# DMX.net
KiCad netlist of a schematic drawn in Altium Designer
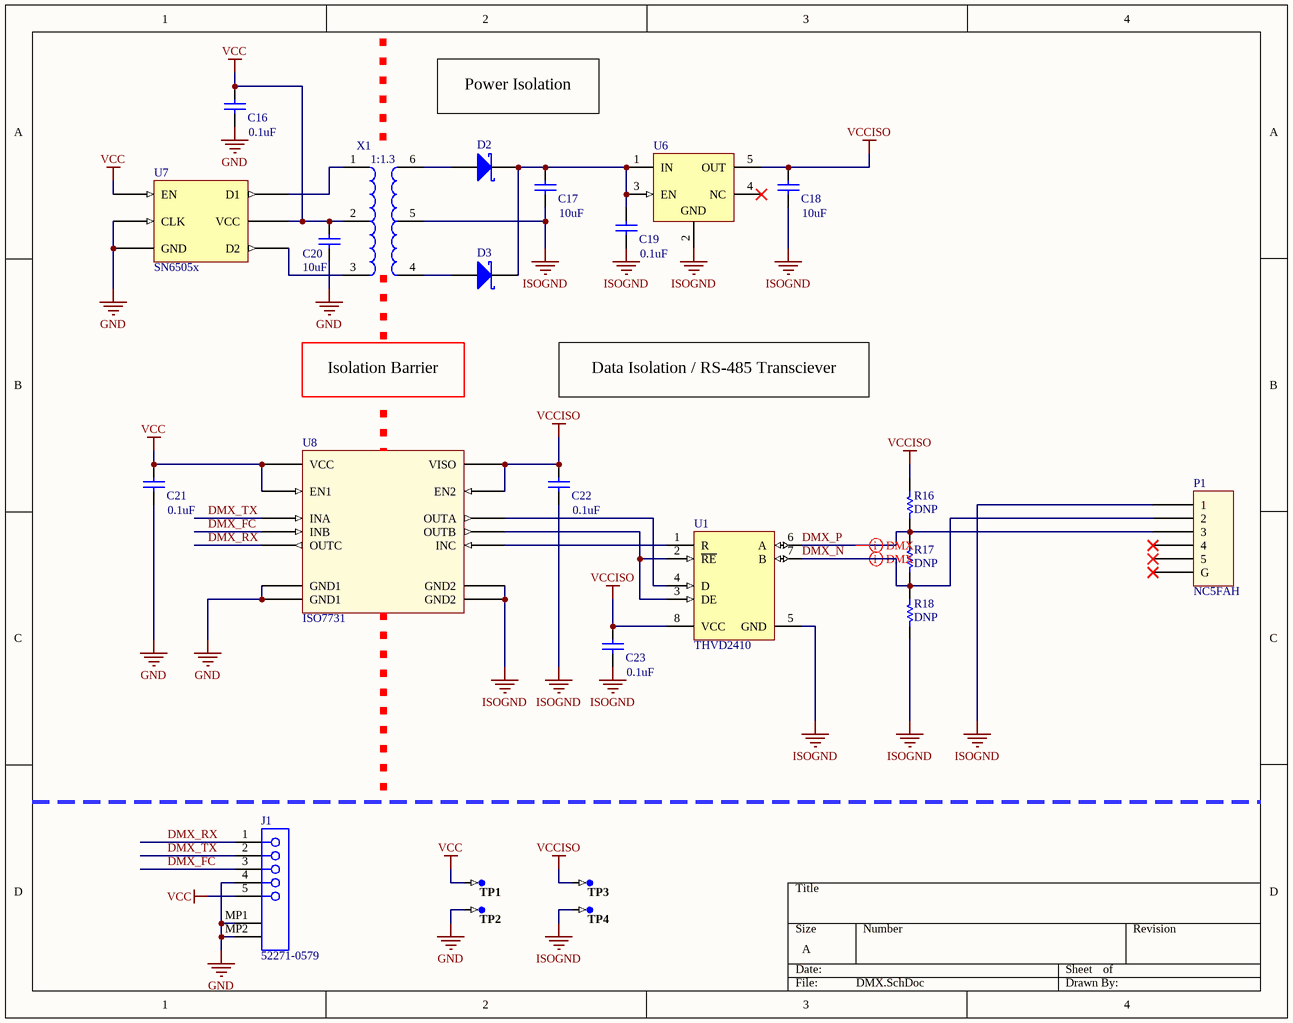
[diagram p0: DMX.SchDoc]

(export (version "E")
  (design (tool "Eeschema 10.0.6"))
  (components
    (comp (ref "C16")
      (value "0.1uF")
      (footprint "CAPC0603(1608)100_L")
      (description "CAP 27pF 16V ±0.5pF 0603 (1608 Metric) Thickness 1mm SMD")
      (fields (field (name "TOLERANCE") "Â±0.5pF"))
      (libsource (lib "Altium Content Vault") (part "CMP-1035-00873-1"))
    )
    (comp (ref "C17")
      (value "10uF")
      (footprint "CAPC0603(1608)100_L")
      (description "CAP 27pF 16V ±0.5pF 0603 (1608 Metric) Thickness 1mm SMD")
      (fields (field (name "TOLERANCE") "Â±0.5pF"))
      (libsource (lib "Altium Content Vault") (part "CMP-1035-00873-1"))
    )
    (comp (ref "C18")
      (value "10uF")
      (footprint "CAPC0603(1608)100_L")
      (description "CAP 27pF 16V ±0.5pF 0603 (1608 Metric) Thickness 1mm SMD")
      (fields (field (name "TOLERANCE") "Â±0.5pF"))
      (libsource (lib "Altium Content Vault") (part "CMP-1035-00873-1"))
    )
    (comp (ref "C19")
      (value "0.1uF")
      (footprint "CAPC0603(1608)100_L")
      (description "CAP 27pF 16V ±0.5pF 0603 (1608 Metric) Thickness 1mm SMD")
      (fields (field (name "TOLERANCE") "Â±0.5pF"))
      (libsource (lib "Altium Content Vault") (part "CMP-1035-00873-1"))
    )
    (comp (ref "C20")
      (value "10uF")
      (footprint "CAPC0603(1608)100_L")
      (description "CAP 27pF 16V ±0.5pF 0603 (1608 Metric) Thickness 1mm SMD")
      (fields (field (name "TOLERANCE") "Â±0.5pF"))
      (libsource (lib "Altium Content Vault") (part "CMP-1035-00873-1"))
    )
    (comp (ref "C21")
      (value "0.1uF")
      (footprint "CAPC0603(1608)100_L")
      (description "CAP 27pF 16V ±0.5pF 0603 (1608 Metric) Thickness 1mm SMD")
      (fields (field (name "TOLERANCE") "Â±0.5pF"))
      (libsource (lib "Altium Content Vault") (part "CMP-1035-00873-1"))
    )
    (comp (ref "C22")
      (value "0.1uF")
      (footprint "CAPC0603(1608)100_L")
      (description "CAP 27pF 16V ±0.5pF 0603 (1608 Metric) Thickness 1mm SMD")
      (fields (field (name "TOLERANCE") "Â±0.5pF"))
      (libsource (lib "Altium Content Vault") (part "CMP-1035-00873-1"))
    )
    (comp (ref "C23")
      (value "0.1uF")
      (footprint "CAPC0603(1608)100_L")
      (description "CAP 27pF 16V ±0.5pF 0603 (1608 Metric) Thickness 1mm SMD")
      (fields (field (name "TOLERANCE") "Â±0.5pF"))
      (libsource (lib "Altium Content Vault") (part "CMP-1035-00873-1"))
    )
    (comp (ref "D2")
      (value "MBR0520L")
      (footprint "ONSC-SOD-123-2-425-04_V")
      (description "Schottky Diode, 20V, 0.2A, 2-pin SOD-123, RoHS, Tape and Reel")
      (fields (field (name "MANUFACTURER") "FairchildSemiconductor"))
      (libsource (lib "Altium Content Vault") (part "CMP-2000-04926-1"))
    )
    (comp (ref "D3")
      (value "MBR0520L")
      (footprint "ONSC-SOD-123-2-425-04_V")
      (description "Schottky Diode, 20V, 0.2A, 2-pin SOD-123, RoHS, Tape and Reel")
      (fields (field (name "MANUFACTURER") "FairchildSemiconductor"))
      (libsource (lib "Altium Content Vault") (part "CMP-2000-04926-1"))
    )
    (comp (ref "J1")
      (value "52271-0579")
      (footprint "MOLX-52271-0579")
      (fields (field (name "MANUFACTURER") "Molex"))
      (libsource (lib "Molex FFC - FPC Connectors (SMT)") (part "52271-0579"))
    )
    (comp (ref "P1") (value "NC5FAH") (footprint "NC5FAH") (libsource (lib "Neutrik") (part "NC5FAH")))
    (comp (ref "R16")
      (value "DNP")
      (footprint "RESC0603(1608)_N")
      (description "300K 0.1W 5% 0603 (1608 Metric)  SMD")
      (fields (field (name "POWER") "0.1 W") (field (name "TOLERANCE") "5 %"))
      (libsource (lib "Altium Content Vault") (part "CMP-1012-00133-1"))
    )
    (comp (ref "R17")
      (value "DNP")
      (footprint "RESC0603(1608)_N")
      (description "300K 0.1W 5% 0603 (1608 Metric)  SMD")
      (fields (field (name "POWER") "0.1 W") (field (name "TOLERANCE") "5 %"))
      (libsource (lib "Altium Content Vault") (part "CMP-1012-00133-1"))
    )
    (comp (ref "R18")
      (value "DNP")
      (footprint "RESC0603(1608)_N")
      (description "300K 0.1W 5% 0603 (1608 Metric)  SMD")
      (fields (field (name "POWER") "0.1 W") (field (name "TOLERANCE") "5 %"))
      (libsource (lib "Altium Content Vault") (part "CMP-1012-00133-1"))
    )
    (comp (ref "TP1")
      (value "TP-SM-C-100")
      (footprint "TP-SM-C-100")
      (description "Test Point, Surface Mount, Circular, Pad Diameter 1 mm")
      (fields (field (name "MANUFACTURER") "No Vendor"))
      (libsource (lib "Altium Content Vault") (part "CMP-0484-00002-2"))
    )
    (comp (ref "TP2")
      (value "TP-SM-C-100")
      (footprint "TP-SM-C-100")
      (description "Test Point, Surface Mount, Circular, Pad Diameter 1 mm")
      (fields (field (name "MANUFACTURER") "No Vendor"))
      (libsource (lib "Altium Content Vault") (part "CMP-0484-00002-2"))
    )
    (comp (ref "TP3")
      (value "TP-SM-C-100")
      (footprint "TP-SM-C-100")
      (description "Test Point, Surface Mount, Circular, Pad Diameter 1 mm")
      (fields (field (name "MANUFACTURER") "No Vendor"))
      (libsource (lib "Altium Content Vault") (part "CMP-0484-00002-2"))
    )
    (comp (ref "TP4")
      (value "TP-SM-C-100")
      (footprint "TP-SM-C-100")
      (description "Test Point, Surface Mount, Circular, Pad Diameter 1 mm")
      (fields (field (name "MANUFACTURER") "No Vendor"))
      (libsource (lib "Altium Content Vault") (part "CMP-0484-00002-2"))
    )
    (comp (ref "U1")
      (value "THVD2410")
      (footprint "D0008A_M")
      (fields (field (name "MANUFACTURER") "Texas Instruments") (field (name "PARTNUMBER") "SN65HVD72DR"))
      (libsource (lib "Altium Content Vault") (part "CMP-0694-00004-2"))
    )
    (comp (ref "U6")
      (value "TPS76333DBVTG4")
      (footprint "TI-DBV5_M")
      (fields (field (name "MANUFACTURER") "Texas Instruments"))
      (libsource (lib "Altium Content Vault") (part "CMP-0394-00562-1"))
    )
    (comp (ref "U7")
      (value "SN6505x")
      (footprint "SOT-23-6")
      (libsource (lib "Texas Instruments") (part "SN6505x"))
    )
    (comp (ref "U8")
      (value "ISO7731")
      (footprint "SOIC (16)")
      (libsource (lib "Texas Instruments") (part "ISO7731"))
    )
    (comp (ref "X1")
      (value "750313638")
      (footprint "750313638")
      (libsource (lib "Wurth Electronics") (part "750313638"))
    )
  )
  (nets
    (net (code "1") (name "/DMX_FC") (class "Default")
      (node (ref "J1") (pin "3") (pinfunction "3_3") (pintype "passive"))
      (node (ref "U8") (pin "4") (pinfunction "INB_4") (pintype "input"))
    )
    (net (code "2") (name "/DMX_N") (class "Default")
      (node (ref "P1") (pin "2") (pinfunction "2_2") (pintype "power_in"))
      (node (ref "R17") (pin "1") (pinfunction "1_1") (pintype "passive"))
      (node (ref "R18") (pin "1") (pinfunction "1_1") (pintype "passive"))
      (node (ref "U1") (pin "7") (pinfunction "B_7") (pintype "bidirectional"))
    )
    (net (code "3") (name "/DMX_P") (class "Default")
      (node (ref "P1") (pin "3") (pinfunction "3_3") (pintype "power_in"))
      (node (ref "R16") (pin "2") (pinfunction "2_2") (pintype "passive"))
      (node (ref "R17") (pin "2") (pinfunction "2_2") (pintype "passive"))
      (node (ref "U1") (pin "6") (pinfunction "A_6") (pintype "bidirectional"))
    )
    (net (code "4") (name "/DMX_RX") (class "Default")
      (node (ref "J1") (pin "1") (pinfunction "1_1") (pintype "passive"))
      (node (ref "U8") (pin "5") (pinfunction "OUTC_5") (pintype "output"))
    )
    (net (code "5") (name "/DMX_TX") (class "Default")
      (node (ref "J1") (pin "2") (pinfunction "2_2") (pintype "passive"))
      (node (ref "U8") (pin "3") (pinfunction "INA_3") (pintype "input"))
    )
    (net (code "6") (name "GND") (class "Default")
      (node (ref "C16") (pin "1") (pinfunction "1_1") (pintype "passive"))
      (node (ref "C20") (pin "1") (pinfunction "1_1") (pintype "passive"))
      (node (ref "C21") (pin "1") (pinfunction "1_1") (pintype "passive"))
      (node (ref "J1") (pin "4") (pinfunction "4_4") (pintype "passive"))
      (node (ref "J1") (pin "MP1") (pinfunction "MP1_MP1") (pintype "passive"))
      (node (ref "J1") (pin "MP2") (pinfunction "MP2_MP2") (pintype "passive"))
      (node (ref "TP2") (pin "1") (pinfunction "1_1") (pintype "input"))
      (node (ref "U7") (pin "4") (pinfunction "GND_4") (pintype "power_in"))
      (node (ref "U7") (pin "6") (pinfunction "CLK_6") (pintype "input"))
      (node (ref "U8") (pin "2") (pinfunction "GND1_2") (pintype "power_in"))
      (node (ref "U8") (pin "8") (pinfunction "GND1_8") (pintype "power_in"))
    )
    (net (code "7") (name "ISOGND") (class "Default")
      (node (ref "C17") (pin "1") (pinfunction "1_1") (pintype "passive"))
      (node (ref "C18") (pin "1") (pinfunction "1_1") (pintype "passive"))
      (node (ref "C19") (pin "1") (pinfunction "1_1") (pintype "passive"))
      (node (ref "C22") (pin "1") (pinfunction "1_1") (pintype "passive"))
      (node (ref "C23") (pin "1") (pinfunction "1_1") (pintype "passive"))
      (node (ref "P1") (pin "1") (pinfunction "1_1") (pintype "power_in"))
      (node (ref "R18") (pin "2") (pinfunction "2_2") (pintype "passive"))
      (node (ref "TP4") (pin "1") (pinfunction "1_1") (pintype "input"))
      (node (ref "U1") (pin "5") (pinfunction "GND_5") (pintype "power_in"))
      (node (ref "U6") (pin "2") (pinfunction "GND_2") (pintype "power_in"))
      (node (ref "U8") (pin "15") (pinfunction "GND2_15") (pintype "power_in"))
      (node (ref "U8") (pin "9") (pinfunction "GND2_9") (pintype "power_in"))
      (node (ref "X1") (pin "5") (pinfunction "5_5") (pintype "passive"))
    )
    (net (code "8") (name "Net-(D2-A)") (class "Default")
      (node (ref "D2") (pin "2") (pinfunction "A_2") (pintype "passive"))
      (node (ref "X1") (pin "6") (pinfunction "6_6") (pintype "passive"))
    )
    (net (code "9") (name "Net-(D2-K)") (class "Default")
      (node (ref "C17") (pin "2") (pinfunction "2_2") (pintype "passive"))
      (node (ref "C19") (pin "2") (pinfunction "2_2") (pintype "passive"))
      (node (ref "D2") (pin "1") (pinfunction "K_1") (pintype "passive"))
      (node (ref "D3") (pin "1") (pinfunction "K_1") (pintype "passive"))
      (node (ref "U6") (pin "1") (pinfunction "IN_1") (pintype "power_in"))
      (node (ref "U6") (pin "3") (pinfunction "EN_3") (pintype "input"))
    )
    (net (code "10") (name "Net-(D3-A)") (class "Default")
      (node (ref "D3") (pin "2") (pinfunction "A_2") (pintype "passive"))
      (node (ref "X1") (pin "4") (pinfunction "4_4") (pintype "passive"))
    )
    (net (code "11") (name "Net-(U1-D)") (class "Default")
      (node (ref "U1") (pin "4") (pinfunction "D_4") (pintype "input"))
      (node (ref "U8") (pin "14") (pinfunction "OUTA_14") (pintype "output"))
    )
    (net (code "12") (name "Net-(U1-DE)") (class "Default")
      (node (ref "U1") (pin "2") (pinfunction "~{RE}_2") (pintype "input"))
      (node (ref "U1") (pin "3") (pinfunction "DE_3") (pintype "input"))
      (node (ref "U8") (pin "13") (pinfunction "OUTB_13") (pintype "output"))
    )
    (net (code "13") (name "Net-(U1-R)") (class "Default")
      (node (ref "U1") (pin "1") (pinfunction "R_1") (pintype "tri_state"))
      (node (ref "U8") (pin "12") (pinfunction "INC_12") (pintype "input"))
    )
    (net (code "14") (name "Net-(U7-D1)") (class "Default")
      (node (ref "U7") (pin "1") (pinfunction "D1_1") (pintype "output"))
      (node (ref "X1") (pin "1") (pinfunction "1_1") (pintype "passive"))
    )
    (net (code "15") (name "Net-(U7-D2)") (class "Default")
      (node (ref "U7") (pin "3") (pinfunction "D2_3") (pintype "output"))
      (node (ref "X1") (pin "3") (pinfunction "3_3") (pintype "passive"))
    )
    (net (code "16") (name "VCC") (class "Default")
      (node (ref "C16") (pin "2") (pinfunction "2_2") (pintype "passive"))
      (node (ref "C20") (pin "2") (pinfunction "2_2") (pintype "passive"))
      (node (ref "C21") (pin "2") (pinfunction "2_2") (pintype "passive"))
      (node (ref "J1") (pin "5") (pinfunction "5_5") (pintype "passive"))
      (node (ref "TP1") (pin "1") (pinfunction "1_1") (pintype "input"))
      (node (ref "U7") (pin "2") (pinfunction "VCC_2") (pintype "power_in"))
      (node (ref "U7") (pin "5") (pinfunction "EN_5") (pintype "input"))
      (node (ref "U8") (pin "1") (pinfunction "VCC_1") (pintype "power_in"))
      (node (ref "U8") (pin "7") (pinfunction "EN1_7") (pintype "input"))
      (node (ref "X1") (pin "2") (pinfunction "2_2") (pintype "passive"))
    )
    (net (code "17") (name "VCCISO") (class "Default")
      (node (ref "C18") (pin "2") (pinfunction "2_2") (pintype "passive"))
      (node (ref "C22") (pin "2") (pinfunction "2_2") (pintype "passive"))
      (node (ref "C23") (pin "2") (pinfunction "2_2") (pintype "passive"))
      (node (ref "R16") (pin "1") (pinfunction "1_1") (pintype "passive"))
      (node (ref "TP3") (pin "1") (pinfunction "1_1") (pintype "input"))
      (node (ref "U1") (pin "8") (pinfunction "VCC_8") (pintype "power_in"))
      (node (ref "U6") (pin "5") (pinfunction "OUT_5") (pintype "power_in"))
      (node (ref "U8") (pin "10") (pinfunction "EN2_10") (pintype "input"))
      (node (ref "U8") (pin "16") (pinfunction "VISO_16") (pintype "power_in"))
    )
    (net (code "18") (name "unconnected-(P1-Pad4)") (class "Default")
      (node (ref "P1") (pin "4") (pinfunction "4_4") (pintype "power_in+no_connect"))
    )
    (net (code "19") (name "unconnected-(P1-Pad5)") (class "Default")
      (node (ref "P1") (pin "5") (pinfunction "5_5") (pintype "power_in+no_connect"))
    )
    (net (code "20") (name "unconnected-(P1-PadG)") (class "Default")
      (node (ref "P1") (pin "G") (pinfunction "G_G") (pintype "power_in+no_connect"))
    )
    (net (code "21") (name "unconnected-(U6-NC-Pad4)") (class "Default")
      (node (ref "U6") (pin "4") (pinfunction "NC_4") (pintype "passive+no_connect"))
    )
    (net (code "22") (name "unconnected-(U8-NC-Pad6)") (class "Default")
      (node (ref "U8") (pin "6") (pinfunction "NC_6") (pintype "passive"))
    )
    (net (code "23") (name "unconnected-(U8-NC-Pad11)") (class "Default")
      (node (ref "U8") (pin "11") (pinfunction "NC_11") (pintype "passive"))
    )
  )
)
